# SCH_555-circuit_2025-03-11.net
KiCad netlist of a schematic drawn in EasyEDA
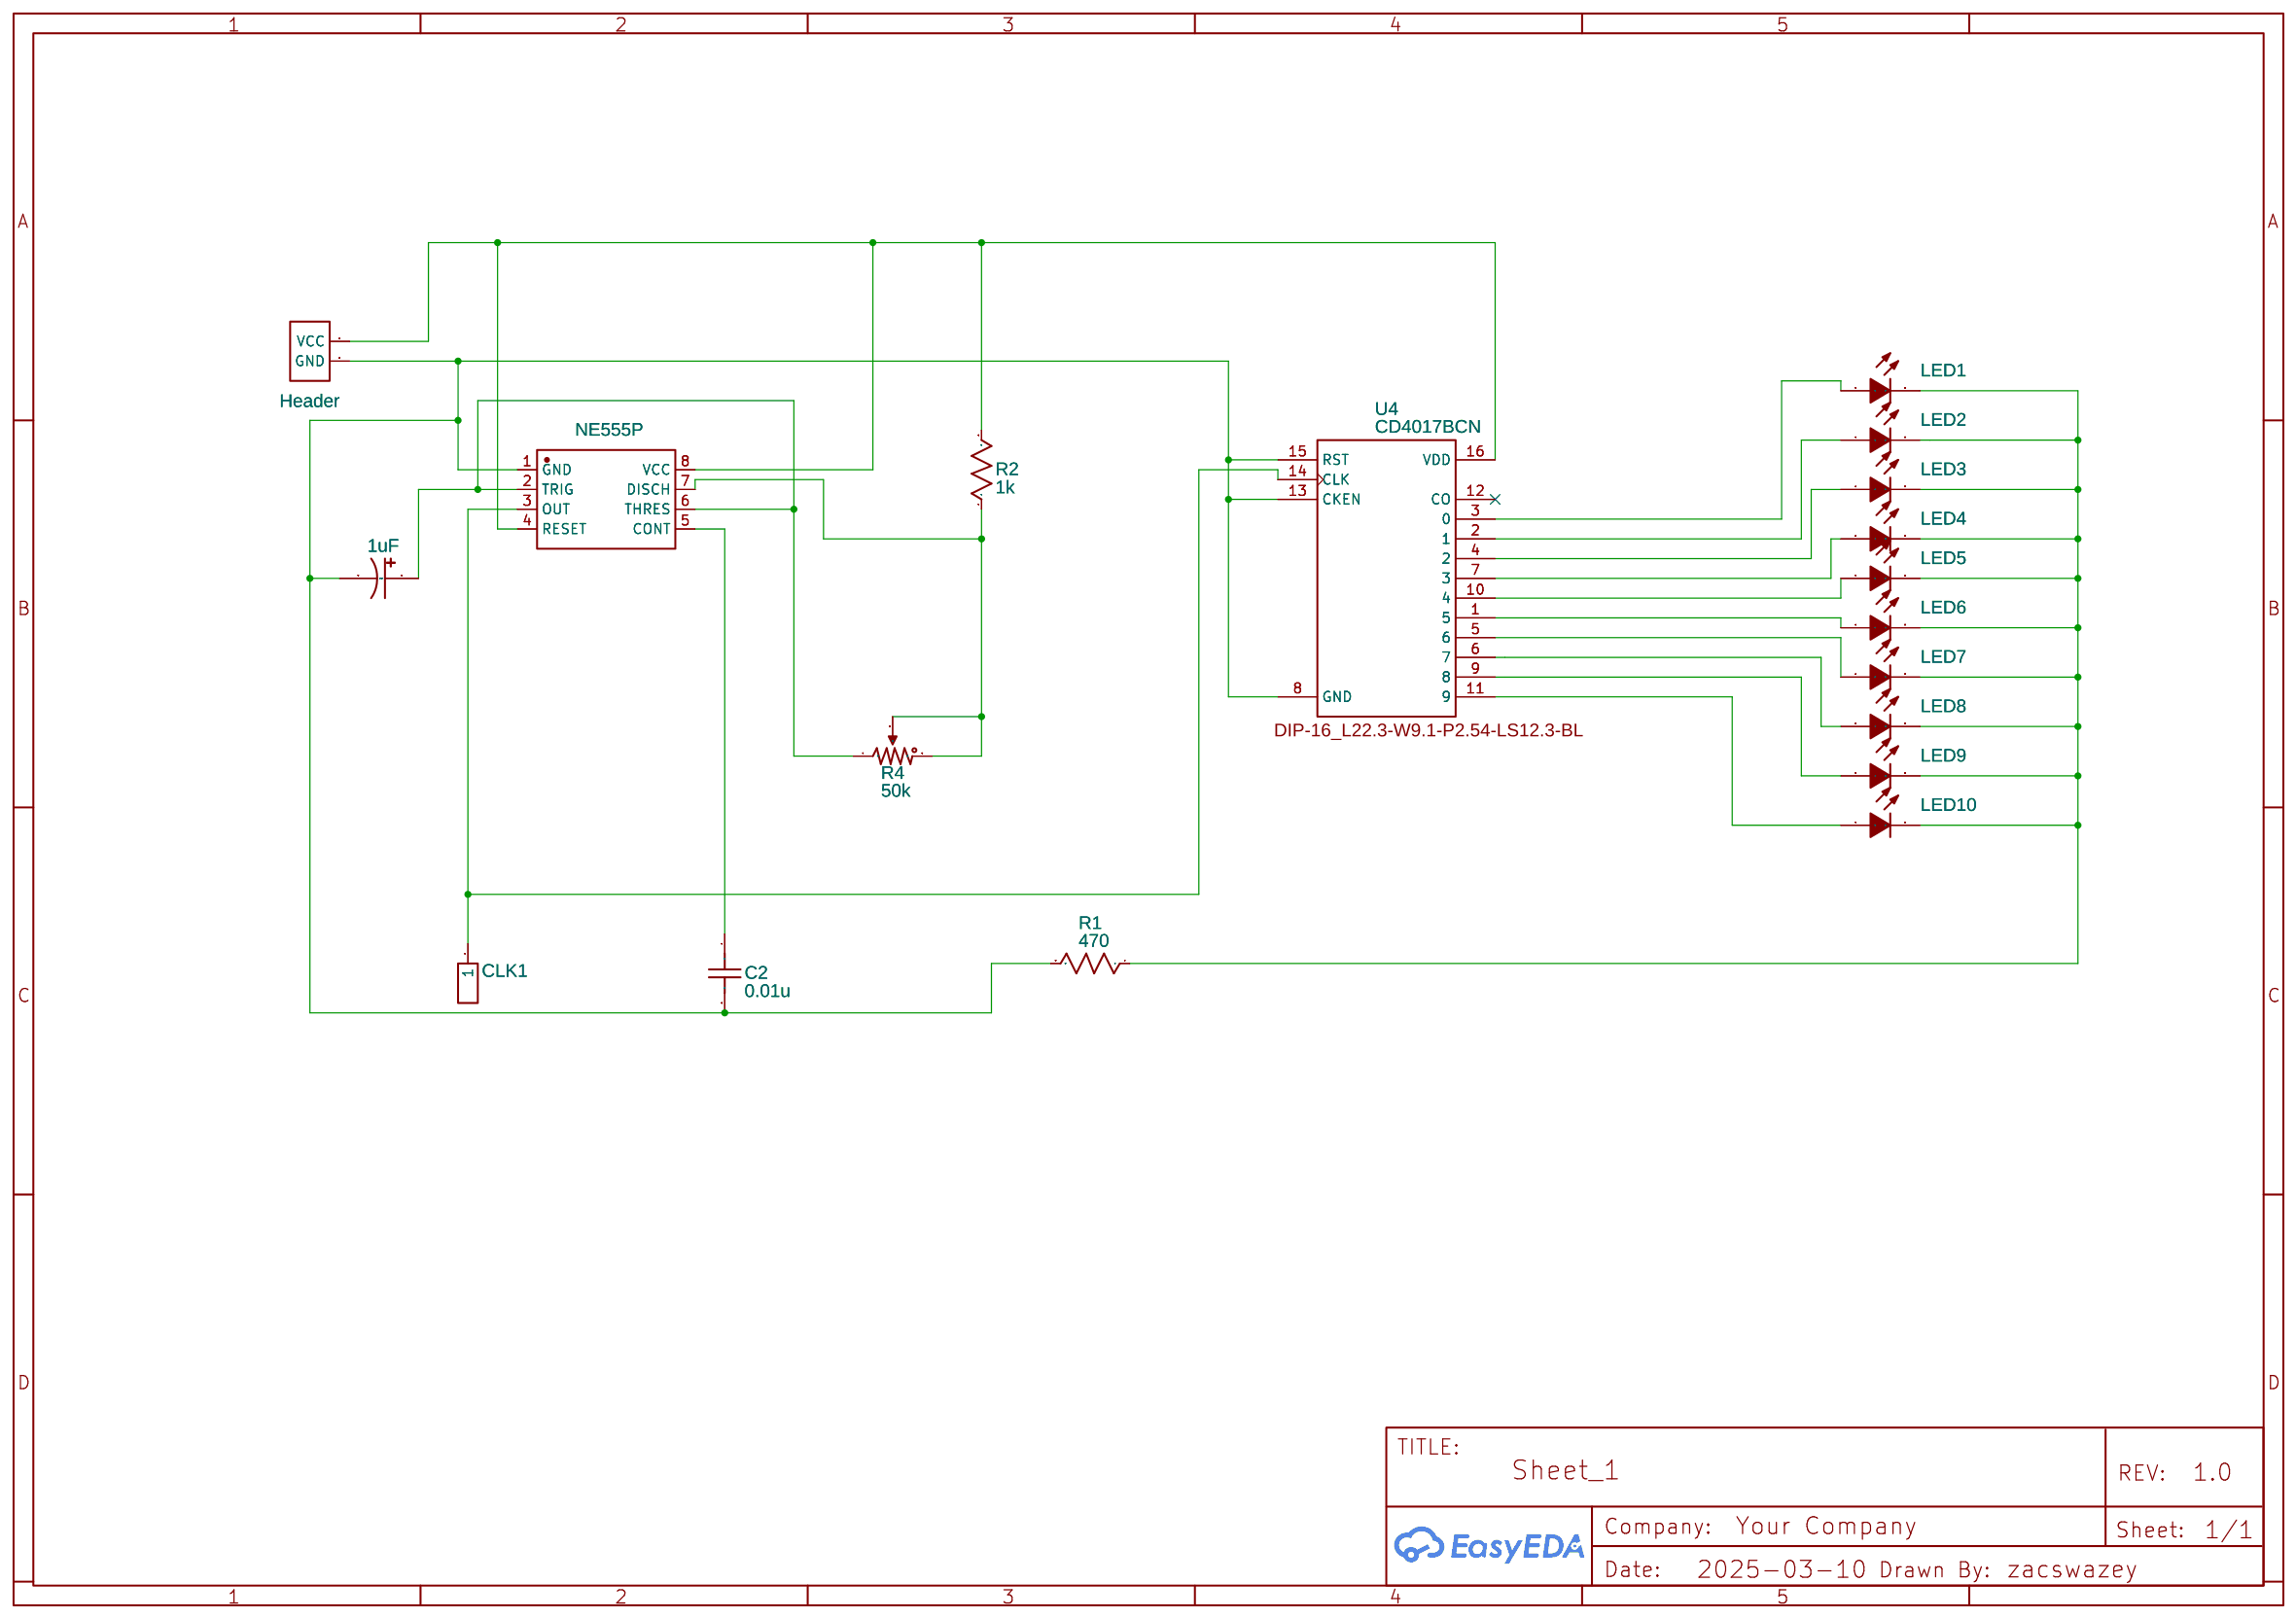
[diagram p0: schematic sheet]

(export (version "E")
  (design (tool "Eeschema 10.0.6"))
  (components
    (comp (ref "C1")
      (value "1uF")
      (fields (field (name "Manufacturer Part") "UVZ1H010MDD") (field (name "Manufacturer") "Nichicon(尼吉康)"))
      (libsource (lib "") (part "UVZ1H010MDD"))
    )
    (comp (ref "C2") (value "0.01u") (libsource (lib "") (part "C_0603_US")))
    (comp (ref "CLK1")
      (value "C81276")
      (fields
        (field (name "Manufacturer Part") "2.54-1*1P针")
        (field (name "Manufacturer") "BOOMELE(Boom Precision Elec)")
      )
      (libsource (lib "") (part "Header-Male-2.54_1x1"))
    )
    (comp (ref "H1") (value "Header") (libsource (lib "") (part "HEADER-FEMALE-2.54_1X2")))
    (comp (ref "LED1") (value "LED_5MM") (libsource (lib "") (part "LED_5MM")))
    (comp (ref "LED2") (value "LED_5MM") (libsource (lib "") (part "LED_5MM")))
    (comp (ref "LED3") (value "LED_5MM") (libsource (lib "") (part "LED_5MM")))
    (comp (ref "LED4") (value "LED_5MM") (libsource (lib "") (part "LED_5MM")))
    (comp (ref "LED5") (value "LED_5MM") (libsource (lib "") (part "LED_5MM")))
    (comp (ref "LED6") (value "LED_5MM") (libsource (lib "") (part "LED_5MM")))
    (comp (ref "LED7") (value "LED_5MM") (libsource (lib "") (part "LED_5MM")))
    (comp (ref "LED8") (value "LED_5MM") (libsource (lib "") (part "LED_5MM")))
    (comp (ref "LED9") (value "LED_5MM") (libsource (lib "") (part "LED_5MM")))
    (comp (ref "LED10") (value "LED_5MM") (libsource (lib "") (part "LED_5MM")))
    (comp (ref "R1")
      (value "470")
      (fields (field (name "Manufacturer Part") "?"))
      (libsource (lib "") (part "Resistor"))
    )
    (comp (ref "R2")
      (value "1k")
      (fields (field (name "Manufacturer Part") "?"))
      (libsource (lib "") (part "Resistor_1"))
    )
    (comp (ref "R4")
      (value "50k")
      (fields (field (name "Manufacturer Part") "?"))
      (libsource (lib "") (part "Potentiometer"))
    )
    (comp (ref "U2")
      (value "NE555P")
      (fields (field (name "Manufacturer") "TI(德州仪器)"))
      (libsource (lib "") (part "NE555P"))
    )
    (comp (ref "U4") (value "CD4017BCN") (libsource (lib "") (part "CD4017BCN")))
  )
  (nets
    (net (code "1") (name "Net-(H1-GND)") (class "Default")
      (node (ref "C1") (pin "2") (pinfunction "2_2") (pintype "unspecified"))
      (node (ref "C2") (pin "2") (pinfunction "2_2") (pintype "unspecified"))
      (node (ref "H1") (pin "2") (pinfunction "GND_2") (pintype "unspecified"))
      (node (ref "R1") (pin "2") (pinfunction "2_2") (pintype "unspecified"))
      (node (ref "U2") (pin "1") (pinfunction "GND_1") (pintype "unspecified"))
      (node (ref "U4") (pin "13") (pinfunction "CKEN_13") (pintype "unspecified"))
      (node (ref "U4") (pin "15") (pinfunction "RST_15") (pintype "unspecified"))
      (node (ref "U4") (pin "8") (pinfunction "GND_8") (pintype "passive"))
    )
    (net (code "2") (name "Net-(H1-VCC)") (class "Default")
      (node (ref "H1") (pin "1") (pinfunction "VCC_1") (pintype "unspecified"))
      (node (ref "R2") (pin "2") (pinfunction "2_2") (pintype "unspecified"))
      (node (ref "U2") (pin "4") (pinfunction "RESET_4") (pintype "unspecified"))
      (node (ref "U2") (pin "8") (pinfunction "VCC_8") (pintype "unspecified"))
      (node (ref "U4") (pin "16") (pinfunction "VDD_16") (pintype "passive"))
    )
    (net (code "3") (name "Net-(LED1-A)") (class "Default")
      (node (ref "LED1") (pin "1") (pinfunction "A_1") (pintype "input"))
      (node (ref "U4") (pin "3") (pinfunction "0_3") (pintype "output"))
    )
    (net (code "4") (name "Net-(LED1-K)") (class "Default")
      (node (ref "LED1") (pin "2") (pinfunction "K_2") (pintype "input"))
      (node (ref "LED10") (pin "2") (pinfunction "K_2") (pintype "input"))
      (node (ref "LED2") (pin "2") (pinfunction "K_2") (pintype "input"))
      (node (ref "LED3") (pin "2") (pinfunction "K_2") (pintype "input"))
      (node (ref "LED4") (pin "2") (pinfunction "K_2") (pintype "input"))
      (node (ref "LED5") (pin "2") (pinfunction "K_2") (pintype "input"))
      (node (ref "LED6") (pin "2") (pinfunction "K_2") (pintype "input"))
      (node (ref "LED7") (pin "2") (pinfunction "K_2") (pintype "input"))
      (node (ref "LED8") (pin "2") (pinfunction "K_2") (pintype "input"))
      (node (ref "LED9") (pin "2") (pinfunction "K_2") (pintype "input"))
      (node (ref "R1") (pin "1") (pinfunction "1_1") (pintype "unspecified"))
    )
    (net (code "5") (name "Net-(LED2-A)") (class "Default")
      (node (ref "LED2") (pin "1") (pinfunction "A_1") (pintype "input"))
      (node (ref "U4") (pin "2") (pinfunction "1_2") (pintype "output"))
    )
    (net (code "6") (name "Net-(LED3-A)") (class "Default")
      (node (ref "LED3") (pin "1") (pinfunction "A_1") (pintype "input"))
      (node (ref "U4") (pin "4") (pinfunction "2_4") (pintype "output"))
    )
    (net (code "7") (name "Net-(LED4-A)") (class "Default")
      (node (ref "LED4") (pin "1") (pinfunction "A_1") (pintype "input"))
      (node (ref "U4") (pin "7") (pinfunction "3_7") (pintype "output"))
    )
    (net (code "8") (name "Net-(LED5-A)") (class "Default")
      (node (ref "LED5") (pin "1") (pinfunction "A_1") (pintype "input"))
      (node (ref "U4") (pin "10") (pinfunction "4_10") (pintype "output"))
    )
    (net (code "9") (name "Net-(LED6-A)") (class "Default")
      (node (ref "LED6") (pin "1") (pinfunction "A_1") (pintype "input"))
      (node (ref "U4") (pin "1") (pinfunction "5_1") (pintype "output"))
    )
    (net (code "10") (name "Net-(LED7-A)") (class "Default")
      (node (ref "LED7") (pin "1") (pinfunction "A_1") (pintype "input"))
      (node (ref "U4") (pin "5") (pinfunction "6_5") (pintype "output"))
    )
    (net (code "11") (name "Net-(LED8-A)") (class "Default")
      (node (ref "LED8") (pin "1") (pinfunction "A_1") (pintype "input"))
      (node (ref "U4") (pin "6") (pinfunction "7_6") (pintype "output"))
    )
    (net (code "12") (name "Net-(LED9-A)") (class "Default")
      (node (ref "LED9") (pin "1") (pinfunction "A_1") (pintype "input"))
      (node (ref "U4") (pin "9") (pinfunction "8_9") (pintype "output"))
    )
    (net (code "13") (name "Net-(LED10-A)") (class "Default")
      (node (ref "LED10") (pin "1") (pinfunction "A_1") (pintype "input"))
      (node (ref "U4") (pin "11") (pinfunction "9_11") (pintype "output"))
    )
    (net (code "14") (name "Net-(R4-2)") (class "Default")
      (node (ref "R2") (pin "1") (pinfunction "1_1") (pintype "unspecified"))
      (node (ref "R4") (pin "2") (pinfunction "3_2") (pintype "unspecified"))
      (node (ref "R4") (pin "3") (pinfunction "2_3") (pintype "unspecified"))
      (node (ref "U2") (pin "7") (pinfunction "DISCH_7") (pintype "unspecified"))
    )
    (net (code "15") (name "Net-(U2-CONT)") (class "Default")
      (node (ref "C2") (pin "1") (pinfunction "1_1") (pintype "unspecified"))
      (node (ref "U2") (pin "5") (pinfunction "CONT_5") (pintype "unspecified"))
    )
    (net (code "16") (name "Net-(U2-OUT)") (class "Default")
      (node (ref "CLK1") (pin "1") (pinfunction "1_1") (pintype "unspecified"))
      (node (ref "U2") (pin "3") (pinfunction "OUT_3") (pintype "unspecified"))
      (node (ref "U4") (pin "14") (pinfunction "CLK_14") (pintype "unspecified"))
    )
    (net (code "17") (name "Net-(U2-THRES)") (class "Default")
      (node (ref "C1") (pin "1") (pinfunction "1_1") (pintype "unspecified"))
      (node (ref "R4") (pin "1") (pinfunction "1_1") (pintype "unspecified"))
      (node (ref "U2") (pin "2") (pinfunction "TRIG_2") (pintype "unspecified"))
      (node (ref "U2") (pin "6") (pinfunction "THRES_6") (pintype "unspecified"))
    )
    (net (code "18") (name "unconnected-(U4-CO-Pad12)") (class "Default")
      (node (ref "U4") (pin "12") (pinfunction "CO_12") (pintype "output+no_connect"))
    )
  )
)
